# OLM-env-sensor.net
KiCad netlist of a schematic drawn in EAGLE
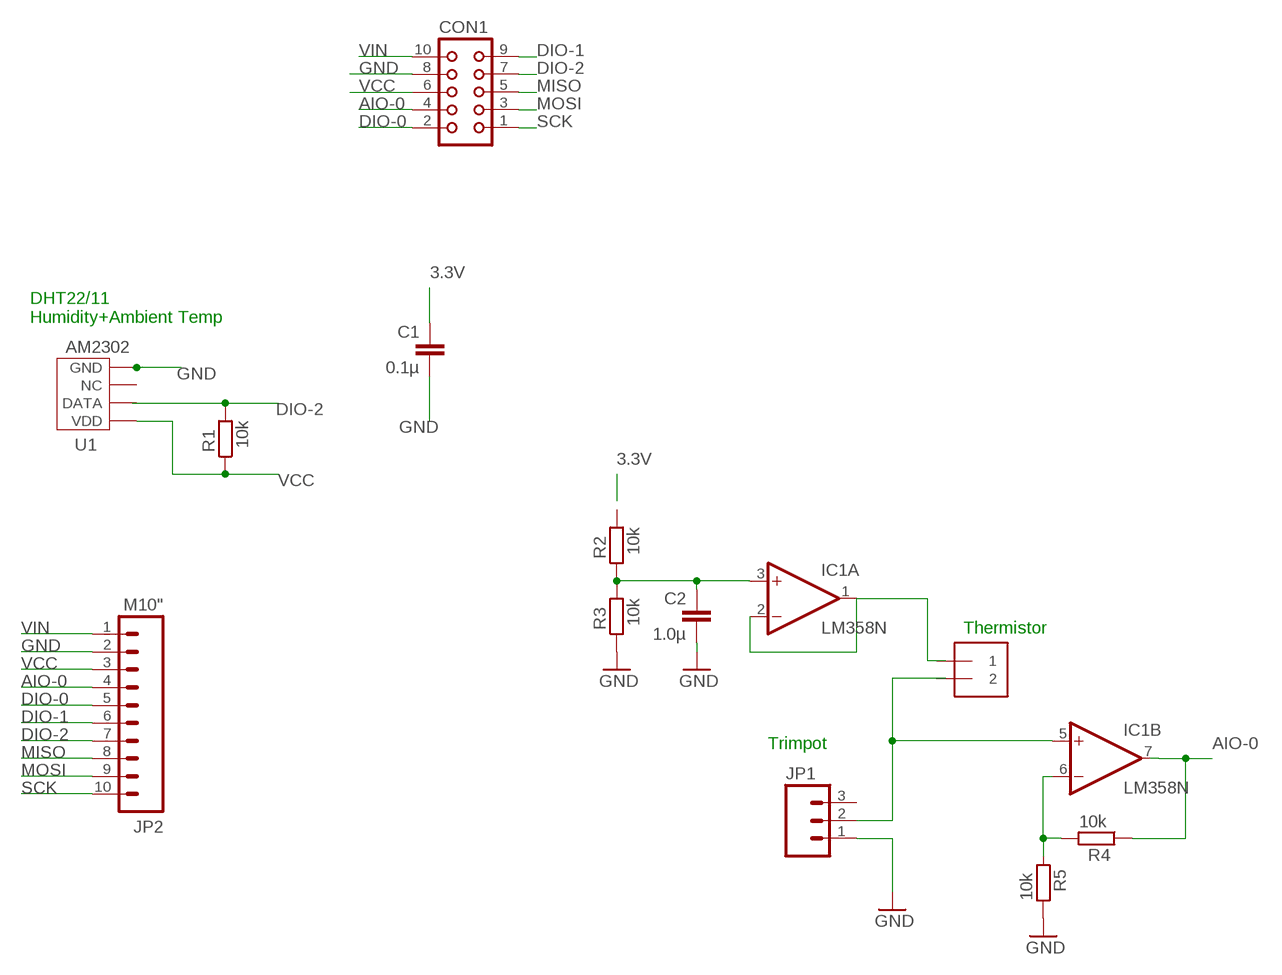
[diagram p0: schematic, sheet 1]

(export (version "E")
  (design (tool "Eeschema 10.0.6"))
  (components
    (comp (ref "C1")
      (value "0.1µ")
      (footprint "eagle-import:C025-024X044")
      (libsource (lib "eagle-import") (part "C-EU025-024X044"))
    )
    (comp (ref "C2")
      (value "1.0µ")
      (footprint "eagle-import:C025-024X044")
      (libsource (lib "eagle-import") (part "C-EU025-024X044"))
    )
    (comp (ref "CON1")
      (value "CON10L")
      (footprint "eagle-import:CON10L")
      (libsource (lib "eagle-import") (part "CON10L"))
    )
    (comp (ref "IC1")
      (value "LM358N")
      (footprint "eagle-import:DIL08")
      (libsource (lib "eagle-import") (part "LM358N"))
    )
    (comp (ref "J1")
      (value "1X2-3.5MM")
      (footprint "eagle-import:1X2-3.5MM")
      (libsource (lib "eagle-import") (part "1X2-3.5MM"))
    )
    (comp (ref "JP1")
      (value "M03PTH")
      (footprint "eagle-import:1X03")
      (libsource (lib "eagle-import") (part "M03PTH"))
    )
    (comp (ref "JP2")
      (value "M10\"")
      (footprint "eagle-import:1X10")
      (libsource (lib "eagle-import") (part "M10{dblquote}"))
    )
    (comp (ref "R1")
      (value "10k")
      (footprint "eagle-import:0204_7")
      (libsource (lib "eagle-import") (part "R-EU_0204/7"))
    )
    (comp (ref "R2")
      (value "10k")
      (footprint "eagle-import:0204_7")
      (libsource (lib "eagle-import") (part "R-EU_0204/7"))
    )
    (comp (ref "R3")
      (value "10k")
      (footprint "eagle-import:0204_7")
      (libsource (lib "eagle-import") (part "R-EU_0204/7"))
    )
    (comp (ref "R4")
      (value "10k")
      (footprint "eagle-import:0204_7")
      (libsource (lib "eagle-import") (part "R-EU_0204/7"))
    )
    (comp (ref "R5")
      (value "10k")
      (footprint "eagle-import:0204_7")
      (libsource (lib "eagle-import") (part "R-EU_0204/7"))
    )
    (comp (ref "U1")
      (value "AM2302")
      (footprint "eagle-import:AM2302")
      (libsource (lib "eagle-import") (part "AM2302"))
    )
  )
  (nets
    (net (code "1") (name "/3.3V") (class "Default")
      (node (ref "C1") (pin "1") (pinfunction "1_1") (pintype "passive"))
    )
    (net (code "2") (name "/AIO-0") (class "Default")
      (node (ref "CON1") (pin "4") (pinfunction "4_4") (pintype "passive"))
      (node (ref "IC1") (pin "5") (pinfunction "+IN_5") (pintype "input"))
      (node (ref "IC1") (pin "7") (pinfunction "OUT_7") (pintype "output"))
      (node (ref "J1") (pin "2") (pinfunction "2_2") (pintype "passive"))
      (node (ref "JP1") (pin "2") (pinfunction "2_2") (pintype "passive"))
      (node (ref "JP2") (pin "4") (pinfunction "4_4") (pintype "passive"))
      (node (ref "R4") (pin "1") (pinfunction "1_1") (pintype "passive"))
    )
    (net (code "3") (name "/DIO-0") (class "Default")
      (node (ref "CON1") (pin "2") (pinfunction "2_2") (pintype "passive"))
      (node (ref "JP2") (pin "5") (pinfunction "5_5") (pintype "passive"))
    )
    (net (code "4") (name "/DIO-1") (class "Default")
      (node (ref "CON1") (pin "9") (pinfunction "9_9") (pintype "passive"))
      (node (ref "JP2") (pin "6") (pinfunction "6_6") (pintype "passive"))
    )
    (net (code "5") (name "/DIO-2") (class "Default")
      (node (ref "CON1") (pin "7") (pinfunction "7_7") (pintype "passive"))
      (node (ref "JP2") (pin "7") (pinfunction "7_7") (pintype "passive"))
      (node (ref "R1") (pin "2") (pinfunction "2_2") (pintype "passive"))
      (node (ref "U1") (pin "P$2") (pinfunction "DATA_P$2") (pintype "bidirectional"))
    )
    (net (code "6") (name "/MISO") (class "Default")
      (node (ref "CON1") (pin "5") (pinfunction "5_5") (pintype "passive"))
      (node (ref "JP2") (pin "8") (pinfunction "8_8") (pintype "passive"))
    )
    (net (code "7") (name "/MOSI") (class "Default")
      (node (ref "CON1") (pin "3") (pinfunction "3_3") (pintype "passive"))
      (node (ref "JP2") (pin "9") (pinfunction "9_9") (pintype "passive"))
    )
    (net (code "8") (name "/SCK") (class "Default")
      (node (ref "CON1") (pin "1") (pinfunction "1_1") (pintype "passive"))
      (node (ref "JP2") (pin "10") (pinfunction "10_10") (pintype "passive"))
    )
    (net (code "9") (name "/VCC") (class "Default")
      (node (ref "CON1") (pin "6") (pinfunction "6_6") (pintype "passive"))
      (node (ref "JP2") (pin "3") (pinfunction "3_3") (pintype "passive"))
      (node (ref "R1") (pin "1") (pinfunction "1_1") (pintype "passive"))
      (node (ref "U1") (pin "P$1") (pinfunction "VDD_P$1") (pintype "power_in"))
    )
    (net (code "10") (name "/VIN") (class "Default")
      (node (ref "CON1") (pin "10") (pinfunction "10_10") (pintype "passive"))
      (node (ref "JP2") (pin "1") (pinfunction "1_1") (pintype "passive"))
    )
    (net (code "11") (name "GND") (class "Default")
      (node (ref "C1") (pin "2") (pinfunction "2_2") (pintype "passive"))
      (node (ref "C2") (pin "2") (pinfunction "2_2") (pintype "passive"))
      (node (ref "CON1") (pin "8") (pinfunction "8_8") (pintype "passive"))
      (node (ref "JP1") (pin "1") (pinfunction "1_1") (pintype "passive"))
      (node (ref "JP2") (pin "2") (pinfunction "2_2") (pintype "passive"))
      (node (ref "R3") (pin "1") (pinfunction "1_1") (pintype "passive"))
      (node (ref "R5") (pin "2") (pinfunction "2_2") (pintype "passive"))
      (node (ref "U1") (pin "P$4") (pinfunction "GND_P$4") (pintype "power_in"))
    )
    (net (code "12") (name "Net-(IC1A-+IN)") (class "Default")
      (node (ref "C2") (pin "1") (pinfunction "1_1") (pintype "passive"))
      (node (ref "IC1") (pin "3") (pinfunction "+IN_3") (pintype "input"))
      (node (ref "R2") (pin "1") (pinfunction "1_1") (pintype "passive"))
      (node (ref "R3") (pin "2") (pinfunction "2_2") (pintype "passive"))
    )
    (net (code "13") (name "Net-(IC1A--IN)") (class "Default")
      (node (ref "IC1") (pin "1") (pinfunction "OUT_1") (pintype "output"))
      (node (ref "IC1") (pin "2") (pinfunction "-IN_2") (pintype "input"))
      (node (ref "J1") (pin "1") (pinfunction "1_1") (pintype "passive"))
    )
    (net (code "14") (name "Net-(IC1B--IN)") (class "Default")
      (node (ref "IC1") (pin "6") (pinfunction "-IN_6") (pintype "input"))
      (node (ref "R4") (pin "2") (pinfunction "2_2") (pintype "passive"))
    )
    (net (code "15") (name "unconnected-(JP1-Pad3)") (class "Default")
      (node (ref "JP1") (pin "3") (pinfunction "3_3") (pintype "passive"))
    )
    (net (code "16") (name "unconnected-(R2-Pad2)") (class "Default")
      (node (ref "R2") (pin "2") (pinfunction "2_2") (pintype "passive"))
    )
    (net (code "17") (name "unconnected-(R5-Pad1)") (class "Default")
      (node (ref "R5") (pin "1") (pinfunction "1_1") (pintype "passive"))
    )
    (net (code "18") (name "unconnected-(U1-NC-PadP$3)") (class "Default")
      (node (ref "U1") (pin "P$3") (pinfunction "NC_P$3") (pintype "no_connect"))
    )
  )
)
